# main.net
KiCad netlist of a schematic drawn in EAGLE
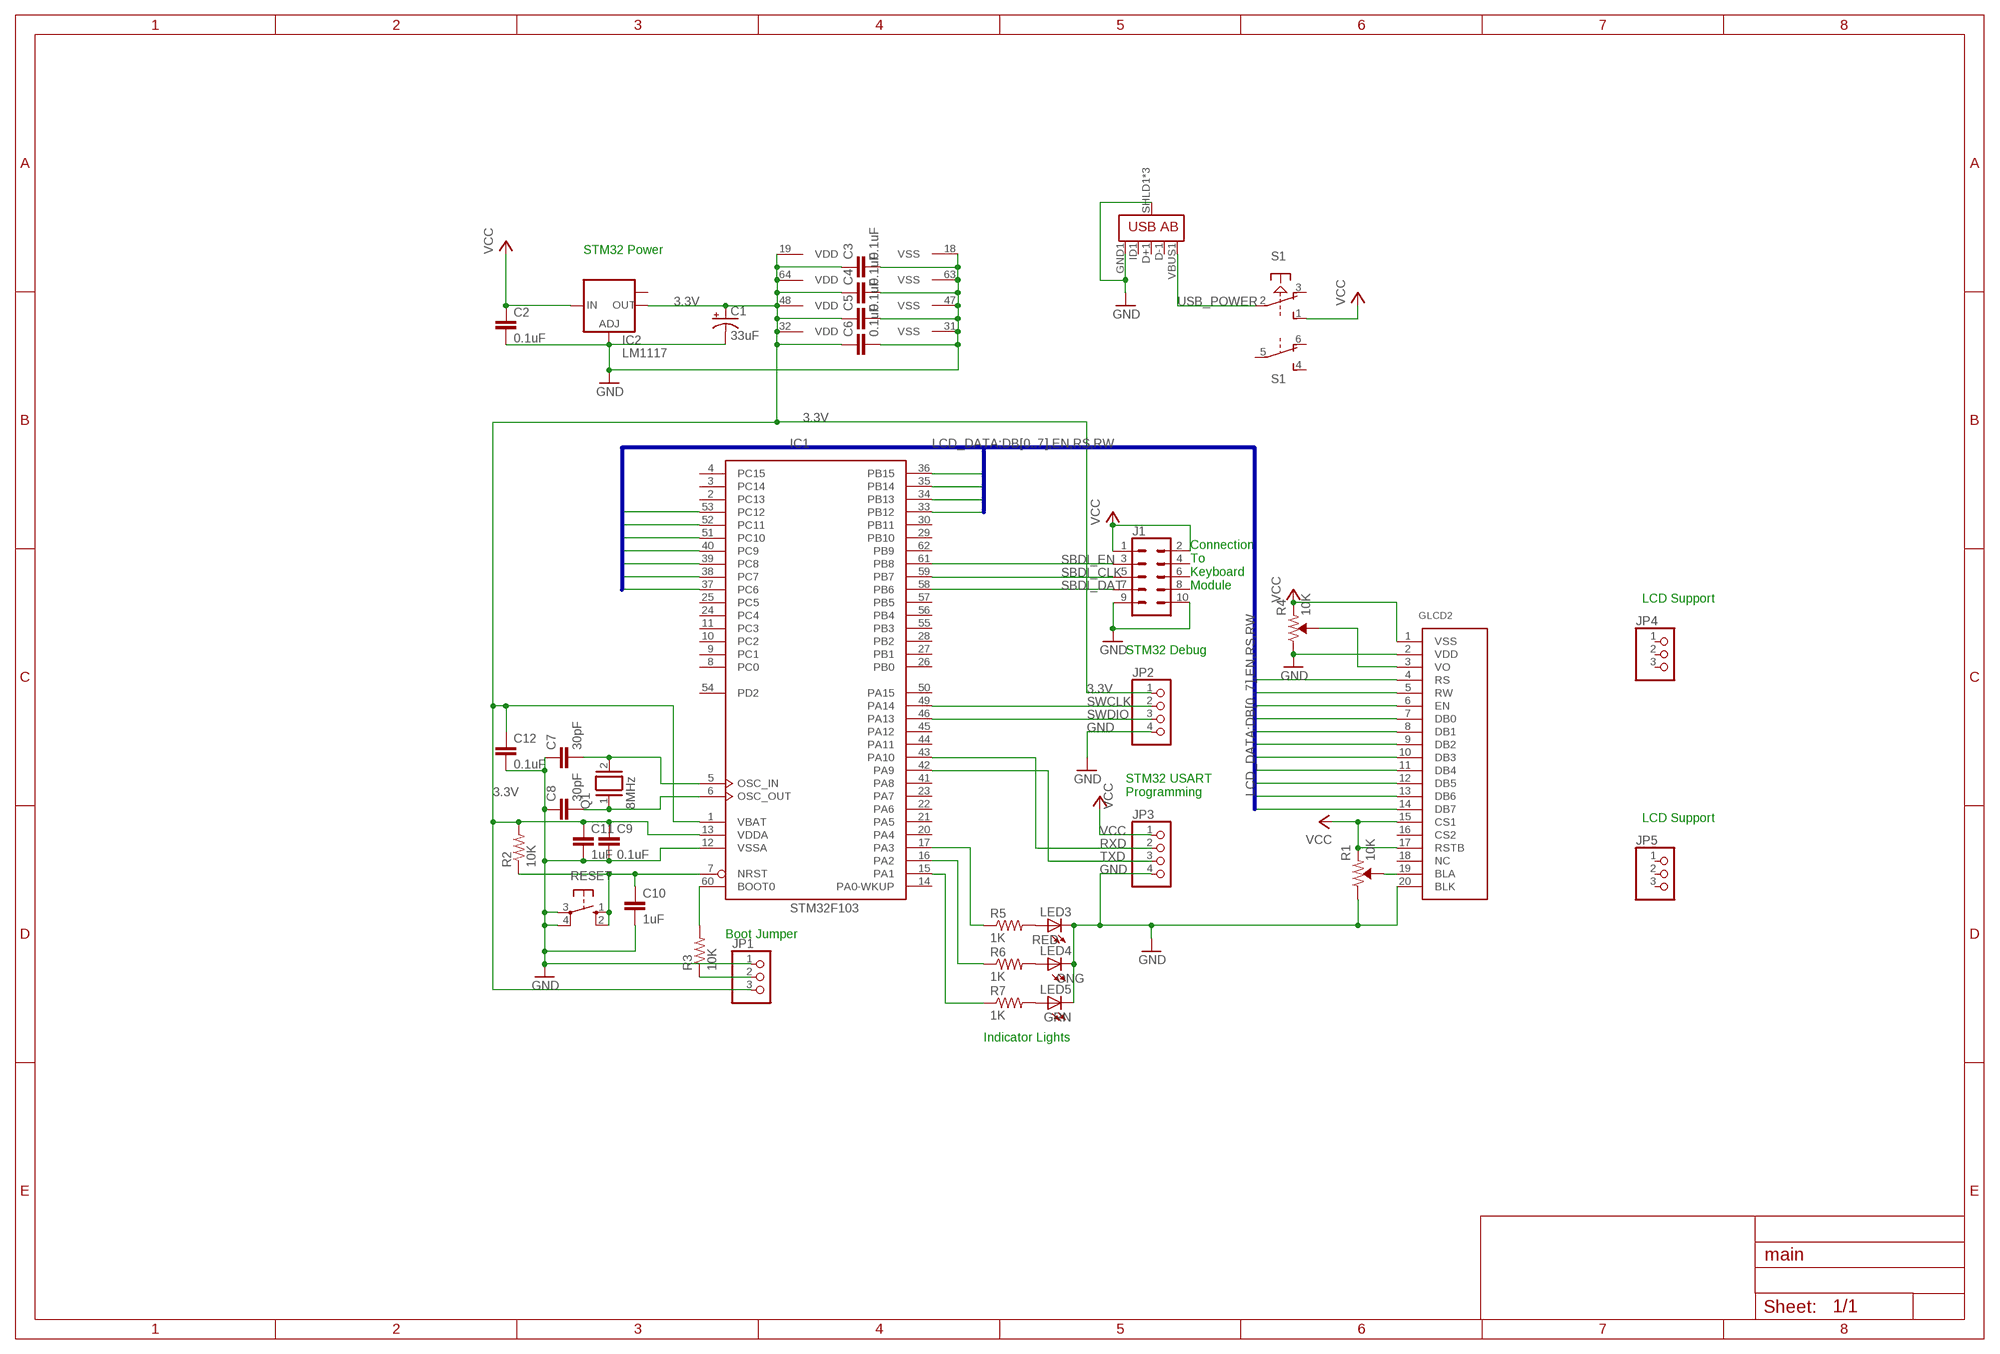
[diagram p0: schematic, sheet 1]

(export (version "E")
  (design (tool "Eeschema 10.0.6"))
  (components
    (comp (ref "C1")
      (value "33uF")
      (footprint "eagle-import:E2-5")
      (libsource (lib "eagle-import") (part "CPOL-USE2-5"))
    )
    (comp (ref "C2")
      (value "0.1uF")
      (footprint "eagle-import:C025-025X050")
      (libsource (lib "eagle-import") (part "C-EU025-025X050"))
    )
    (comp (ref "C3")
      (value "0.1uF")
      (footprint "eagle-import:C025-025X050")
      (libsource (lib "eagle-import") (part "C-EU025-025X050"))
    )
    (comp (ref "C4")
      (value "0.1uF")
      (footprint "eagle-import:C025-025X050")
      (libsource (lib "eagle-import") (part "C-EU025-025X050"))
    )
    (comp (ref "C5")
      (value "0.1uF")
      (footprint "eagle-import:C025-025X050")
      (libsource (lib "eagle-import") (part "C-EU025-025X050"))
    )
    (comp (ref "C6")
      (value "0.1uF")
      (footprint "eagle-import:C025-025X050")
      (libsource (lib "eagle-import") (part "C-EU025-025X050"))
    )
    (comp (ref "C7")
      (value "30pF")
      (footprint "eagle-import:C025-025X050")
      (libsource (lib "eagle-import") (part "C-EU025-025X050"))
    )
    (comp (ref "C8")
      (value "30pF")
      (footprint "eagle-import:C025-025X050")
      (libsource (lib "eagle-import") (part "C-EU025-025X050"))
    )
    (comp (ref "C9")
      (value "0.1uF")
      (footprint "eagle-import:C025-025X050")
      (libsource (lib "eagle-import") (part "C-EU025-025X050"))
    )
    (comp (ref "C10")
      (value "1uF")
      (footprint "eagle-import:C025-025X050")
      (libsource (lib "eagle-import") (part "C-EU025-025X050"))
    )
    (comp (ref "C11")
      (value "1uF")
      (footprint "eagle-import:C025-025X050")
      (libsource (lib "eagle-import") (part "C-EU025-025X050"))
    )
    (comp (ref "C12")
      (value "0.1uF")
      (footprint "eagle-import:C025-025X050")
      (libsource (lib "eagle-import") (part "C-EU025-025X050"))
    )
    (comp (ref "GLCD2")
      (value "LCD128X64")
      (footprint "eagle-import:GLCD_TRULY_128X64_20_PINES")
      (libsource (lib "eagle-import") (part "LCD128X64"))
    )
    (comp (ref "IC1")
      (value "STM32F103")
      (footprint "eagle-import:LQFP64")
      (libsource (lib "eagle-import") (part "STM32F103RTC"))
    )
    (comp (ref "IC2")
      (value "LM1117")
      (footprint "eagle-import:SOT223")
      (libsource (lib "eagle-import") (part "LM1117IMPX-ADJ"))
    )
    (comp (ref "J1")
      (value "CONN_05X2SHD_LOCK")
      (footprint "eagle-import:2X5-SHROUDED_LOCK")
      (libsource (lib "eagle-import") (part "CONN_05X2SHD_LOCK"))
    )
    (comp (ref "JP1")
      (value "PINHD-1X3")
      (footprint "eagle-import:1X03")
      (libsource (lib "eagle-import") (part "PINHD-1X3"))
    )
    (comp (ref "JP2")
      (value "PINHD-1X4")
      (footprint "eagle-import:1X04")
      (libsource (lib "eagle-import") (part "PINHD-1X4"))
    )
    (comp (ref "JP3")
      (value "PINHD-1X4")
      (footprint "eagle-import:1X04")
      (libsource (lib "eagle-import") (part "PINHD-1X4"))
    )
    (comp (ref "JP4")
      (value "PINHD-1X3")
      (footprint "eagle-import:1X03")
      (libsource (lib "eagle-import") (part "PINHD-1X3"))
    )
    (comp (ref "JP5")
      (value "PINHD-1X3")
      (footprint "eagle-import:1X03")
      (libsource (lib "eagle-import") (part "PINHD-1X3"))
    )
    (comp (ref "LED3")
      (value "RED")
      (footprint "eagle-import:LED5MM")
      (libsource (lib "eagle-import") (part "LED5MM"))
    )
    (comp (ref "LED4")
      (value "ONG")
      (footprint "eagle-import:LED5MM")
      (libsource (lib "eagle-import") (part "LED5MM"))
    )
    (comp (ref "LED5")
      (value "GRN")
      (footprint "eagle-import:LED5MM")
      (libsource (lib "eagle-import") (part "LED5MM"))
    )
    (comp (ref "Q1")
      (value "8MHz")
      (footprint "eagle-import:QS")
      (libsource (lib "eagle-import") (part "XTAL/S"))
    )
    (comp (ref "R1")
      (value "10K")
      (footprint "eagle-import:TRIMPOT-PTH-3386U")
      (libsource (lib "eagle-import") (part "TRIMPOT-KNOB"))
    )
    (comp (ref "R2")
      (value "10K")
      (footprint "eagle-import:0204_7")
      (libsource (lib "eagle-import") (part "R-US_0204/7"))
    )
    (comp (ref "R3")
      (value "10K")
      (footprint "eagle-import:0204_7")
      (libsource (lib "eagle-import") (part "R-US_0204/7"))
    )
    (comp (ref "R4")
      (value "10K")
      (footprint "eagle-import:TRIMPOT-PTH-3386U")
      (libsource (lib "eagle-import") (part "TRIMPOT-KNOB"))
    )
    (comp (ref "R5")
      (value "1K")
      (footprint "eagle-import:0204_7")
      (libsource (lib "eagle-import") (part "R-US_0204/7"))
    )
    (comp (ref "R6")
      (value "1K")
      (footprint "eagle-import:0204_7")
      (libsource (lib "eagle-import") (part "R-US_0204/7"))
    )
    (comp (ref "R7")
      (value "1K")
      (footprint "eagle-import:0204_7")
      (libsource (lib "eagle-import") (part "R-US_0204/7"))
    )
    (comp (ref "RESET")
      (value "10-XX")
      (footprint "eagle-import:B3F-10XX")
      (fields (field (name "MPN") "B3F-1000"))
      (libsource (lib "eagle-import") (part "10-XX"))
    )
    (comp (ref "S1")
      (value "PVA2R")
      (footprint "eagle-import:PVA2R")
      (libsource (lib "eagle-import") (part "PVA2R"))
    )
    (comp (ref "U1")
      (value "USB_AB_SMT")
      (footprint "eagle-import:USB-AB-MICRO-SMD")
      (libsource (lib "eagle-import") (part "USB_AB_SMT"))
    )
  )
  (nets
    (net (code "1") (name "/3.3V") (class "Default")
      (node (ref "C1") (pin "+") (pinfunction "+_+") (pintype "passive"))
      (node (ref "C11") (pin "1") (pinfunction "1_1") (pintype "passive"))
      (node (ref "C12") (pin "1") (pinfunction "1_1") (pintype "passive"))
      (node (ref "C3") (pin "1") (pinfunction "1_1") (pintype "passive"))
      (node (ref "C4") (pin "1") (pinfunction "1_1") (pintype "passive"))
      (node (ref "C5") (pin "1") (pinfunction "1_1") (pintype "passive"))
      (node (ref "C6") (pin "1") (pinfunction "1_1") (pintype "passive"))
      (node (ref "C9") (pin "1") (pinfunction "1_1") (pintype "passive"))
      (node (ref "IC1") (pin "1") (pinfunction "VBAT_1") (pintype "power_in"))
      (node (ref "IC1") (pin "13") (pinfunction "VDDA_13") (pintype "power_in"))
      (node (ref "IC1") (pin "19") (pinfunction "VDD_19") (pintype "power_in"))
      (node (ref "IC1") (pin "32") (pinfunction "VDD_32") (pintype "power_in"))
      (node (ref "IC1") (pin "48") (pinfunction "VDD_48") (pintype "power_in"))
      (node (ref "IC1") (pin "64") (pinfunction "VDD_64") (pintype "power_in"))
      (node (ref "IC2") (pin "2") (pinfunction "OUT_2") (pintype "passive"))
      (node (ref "JP1") (pin "3") (pinfunction "3_3") (pintype "passive"))
      (node (ref "JP2") (pin "1") (pinfunction "1_1") (pintype "passive"))
      (node (ref "R2") (pin "2") (pinfunction "2_2") (pintype "passive"))
    )
    (net (code "2") (name "/DB0") (class "Default")
      (node (ref "GLCD2") (pin "7") (pinfunction "DB0_7") (pintype "bidirectional"))
      (node (ref "IC1") (pin "33") (pinfunction "PB12_33") (pintype "bidirectional"))
    )
    (net (code "3") (name "/DB1") (class "Default")
      (node (ref "GLCD2") (pin "8") (pinfunction "DB1_8") (pintype "bidirectional"))
      (node (ref "IC1") (pin "34") (pinfunction "PB13_34") (pintype "bidirectional"))
    )
    (net (code "4") (name "/DB2") (class "Default")
      (node (ref "GLCD2") (pin "9") (pinfunction "DB2_9") (pintype "bidirectional"))
      (node (ref "IC1") (pin "35") (pinfunction "PB14_35") (pintype "bidirectional"))
    )
    (net (code "5") (name "/DB3") (class "Default")
      (node (ref "GLCD2") (pin "10") (pinfunction "DB3_10") (pintype "bidirectional"))
      (node (ref "IC1") (pin "36") (pinfunction "PB15_36") (pintype "bidirectional"))
    )
    (net (code "6") (name "/DB4") (class "Default")
      (node (ref "GLCD2") (pin "11") (pinfunction "DB4_11") (pintype "bidirectional"))
      (node (ref "IC1") (pin "37") (pinfunction "PC6_37") (pintype "bidirectional"))
    )
    (net (code "7") (name "/DB5") (class "Default")
      (node (ref "GLCD2") (pin "12") (pinfunction "DB5_12") (pintype "bidirectional"))
      (node (ref "IC1") (pin "38") (pinfunction "PC7_38") (pintype "bidirectional"))
    )
    (net (code "8") (name "/DB6") (class "Default")
      (node (ref "GLCD2") (pin "13") (pinfunction "DB6_13") (pintype "bidirectional"))
      (node (ref "IC1") (pin "39") (pinfunction "PC8_39") (pintype "bidirectional"))
    )
    (net (code "9") (name "/DB7") (class "Default")
      (node (ref "GLCD2") (pin "14") (pinfunction "DB7_14") (pintype "bidirectional"))
      (node (ref "IC1") (pin "40") (pinfunction "PC9_40") (pintype "bidirectional"))
    )
    (net (code "10") (name "/EN") (class "Default")
      (node (ref "GLCD2") (pin "6") (pinfunction "EN_6") (pintype "bidirectional"))
      (node (ref "IC1") (pin "53") (pinfunction "PC12_53") (pintype "bidirectional"))
    )
    (net (code "11") (name "/RS") (class "Default")
      (node (ref "GLCD2") (pin "4") (pinfunction "RS_4") (pintype "bidirectional"))
      (node (ref "IC1") (pin "51") (pinfunction "PC10_51") (pintype "bidirectional"))
    )
    (net (code "12") (name "/RW") (class "Default")
      (node (ref "GLCD2") (pin "5") (pinfunction "RW_5") (pintype "bidirectional"))
      (node (ref "IC1") (pin "52") (pinfunction "PC11_52") (pintype "bidirectional"))
    )
    (net (code "13") (name "/RXD") (class "Default")
      (node (ref "IC1") (pin "43") (pinfunction "PA10_43") (pintype "bidirectional"))
      (node (ref "JP3") (pin "2") (pinfunction "2_2") (pintype "passive"))
    )
    (net (code "14") (name "/SBDI_CLK") (class "Default")
      (node (ref "IC1") (pin "59") (pinfunction "PB7_59") (pintype "bidirectional"))
      (node (ref "J1") (pin "5") (pinfunction "5_5") (pintype "passive"))
    )
    (net (code "15") (name "/SBDI_DAT") (class "Default")
      (node (ref "IC1") (pin "58") (pinfunction "PB6_58") (pintype "bidirectional"))
      (node (ref "J1") (pin "7") (pinfunction "7_7") (pintype "passive"))
    )
    (net (code "16") (name "/SBDI_EN") (class "Default")
      (node (ref "IC1") (pin "61") (pinfunction "PB8_61") (pintype "bidirectional"))
      (node (ref "J1") (pin "3") (pinfunction "3_3") (pintype "passive"))
    )
    (net (code "17") (name "/SWCLK") (class "Default")
      (node (ref "IC1") (pin "49") (pinfunction "PA14_49") (pintype "bidirectional"))
      (node (ref "JP2") (pin "2") (pinfunction "2_2") (pintype "passive"))
    )
    (net (code "18") (name "/SWDIO") (class "Default")
      (node (ref "IC1") (pin "46") (pinfunction "PA13_46") (pintype "bidirectional"))
      (node (ref "JP2") (pin "3") (pinfunction "3_3") (pintype "passive"))
    )
    (net (code "19") (name "/TXD") (class "Default")
      (node (ref "IC1") (pin "42") (pinfunction "PA9_42") (pintype "bidirectional"))
      (node (ref "JP3") (pin "3") (pinfunction "3_3") (pintype "passive"))
    )
    (net (code "20") (name "/USB_POWER") (class "Default")
      (node (ref "S1") (pin "2") (pinfunction "P_2") (pintype "passive"))
      (node (ref "U1") (pin "VBUS1") (pinfunction "VBUS_VBUS1") (pintype "power_in"))
    )
    (net (code "22") (name "GND") (class "Default")
      (node (ref "C1") (pin "-") (pinfunction "-_-") (pintype "passive"))
      (node (ref "C10") (pin "2") (pinfunction "2_2") (pintype "passive"))
      (node (ref "C11") (pin "2") (pinfunction "2_2") (pintype "passive"))
      (node (ref "C12") (pin "2") (pinfunction "2_2") (pintype "passive"))
      (node (ref "C2") (pin "2") (pinfunction "2_2") (pintype "passive"))
      (node (ref "C3") (pin "2") (pinfunction "2_2") (pintype "passive"))
      (node (ref "C4") (pin "2") (pinfunction "2_2") (pintype "passive"))
      (node (ref "C5") (pin "2") (pinfunction "2_2") (pintype "passive"))
      (node (ref "C6") (pin "2") (pinfunction "2_2") (pintype "passive"))
      (node (ref "C7") (pin "1") (pinfunction "1_1") (pintype "passive"))
      (node (ref "C8") (pin "1") (pinfunction "1_1") (pintype "passive"))
      (node (ref "C9") (pin "2") (pinfunction "2_2") (pintype "passive"))
      (node (ref "GLCD2") (pin "2") (pinfunction "VDD_2") (pintype "power_in"))
      (node (ref "GLCD2") (pin "20") (pinfunction "BLK_20") (pintype "power_in"))
      (node (ref "IC1") (pin "12") (pinfunction "VSSA_12") (pintype "power_in"))
      (node (ref "IC1") (pin "18") (pinfunction "VSS_18") (pintype "power_in"))
      (node (ref "IC1") (pin "31") (pinfunction "VSS_31") (pintype "power_in"))
      (node (ref "IC1") (pin "47") (pinfunction "VSS_47") (pintype "power_in"))
      (node (ref "IC1") (pin "63") (pinfunction "VSS_63") (pintype "power_in"))
      (node (ref "IC2") (pin "1") (pinfunction "ADJ_1") (pintype "input"))
      (node (ref "J1") (pin "10") (pinfunction "10_10") (pintype "passive"))
      (node (ref "J1") (pin "9") (pinfunction "9_9") (pintype "passive"))
      (node (ref "JP1") (pin "1") (pinfunction "1_1") (pintype "passive"))
      (node (ref "JP2") (pin "4") (pinfunction "4_4") (pintype "passive"))
      (node (ref "JP3") (pin "4") (pinfunction "4_4") (pintype "passive"))
      (node (ref "LED3") (pin "K") (pinfunction "C_K") (pintype "passive"))
      (node (ref "LED4") (pin "K") (pinfunction "C_K") (pintype "passive"))
      (node (ref "LED5") (pin "K") (pinfunction "C_K") (pintype "passive"))
      (node (ref "R1") (pin "1") (pinfunction "1_1") (pintype "passive"))
      (node (ref "R4") (pin "1") (pinfunction "1_1") (pintype "passive"))
      (node (ref "RESET") (pin "3") (pinfunction "P_3") (pintype "passive"))
      (node (ref "RESET") (pin "4") (pinfunction "P1_4") (pintype "passive"))
      (node (ref "U1") (pin "GND1") (pinfunction "GND_GND1") (pintype "power_in"))
      (node (ref "U1") (pin "SHLD1") (pinfunction "SHIELD_SHLD1") (pintype "bidirectional"))
      (node (ref "U1") (pin "SHLD2") (pinfunction "SHIELD_SHLD2") (pintype "bidirectional"))
      (node (ref "U1") (pin "SHLD3") (pinfunction "SHIELD_SHLD3") (pintype "bidirectional"))
    )
    (net (code "23") (name "Net-(GLCD2-BLA)") (class "Default")
      (node (ref "GLCD2") (pin "19") (pinfunction "BLA_19") (pintype "power_in"))
      (node (ref "R1") (pin "2") (pinfunction "2_2") (pintype "passive"))
    )
    (net (code "24") (name "Net-(GLCD2-VO)") (class "Default")
      (node (ref "GLCD2") (pin "3") (pinfunction "VO_3") (pintype "bidirectional"))
      (node (ref "R4") (pin "2") (pinfunction "2_2") (pintype "passive"))
    )
    (net (code "25") (name "Net-(IC1A-BOOT0)") (class "Default")
      (node (ref "IC1") (pin "60") (pinfunction "BOOT0_60") (pintype "input"))
      (node (ref "R3") (pin "2") (pinfunction "2_2") (pintype "passive"))
    )
    (net (code "26") (name "Net-(IC1A-NRST)") (class "Default")
      (node (ref "C10") (pin "1") (pinfunction "1_1") (pintype "passive"))
      (node (ref "IC1") (pin "7") (pinfunction "NRST_7") (pintype "bidirectional"))
      (node (ref "R2") (pin "1") (pinfunction "1_1") (pintype "passive"))
      (node (ref "RESET") (pin "1") (pinfunction "S_1") (pintype "passive"))
      (node (ref "RESET") (pin "2") (pinfunction "S1_2") (pintype "passive"))
    )
    (net (code "27") (name "Net-(IC1A-OSC_IN)") (class "Default")
      (node (ref "C7") (pin "2") (pinfunction "2_2") (pintype "passive"))
      (node (ref "IC1") (pin "5") (pinfunction "OSC_IN_5") (pintype "bidirectional"))
      (node (ref "Q1") (pin "2") (pinfunction "2_2") (pintype "passive"))
    )
    (net (code "28") (name "Net-(IC1A-OSC_OUT)") (class "Default")
      (node (ref "C8") (pin "2") (pinfunction "2_2") (pintype "passive"))
      (node (ref "IC1") (pin "6") (pinfunction "OSC_OUT_6") (pintype "bidirectional"))
      (node (ref "Q1") (pin "1") (pinfunction "1_1") (pintype "passive"))
    )
    (net (code "29") (name "Net-(IC1A-PA1)") (class "Default")
      (node (ref "IC1") (pin "15") (pinfunction "PA1_15") (pintype "bidirectional"))
      (node (ref "R7") (pin "1") (pinfunction "1_1") (pintype "passive"))
    )
    (net (code "30") (name "Net-(IC1A-PA2)") (class "Default")
      (node (ref "IC1") (pin "16") (pinfunction "PA2_16") (pintype "bidirectional"))
      (node (ref "R6") (pin "1") (pinfunction "1_1") (pintype "passive"))
    )
    (net (code "31") (name "Net-(IC1A-PA3)") (class "Default")
      (node (ref "IC1") (pin "17") (pinfunction "PA3_17") (pintype "bidirectional"))
      (node (ref "R5") (pin "1") (pinfunction "1_1") (pintype "passive"))
    )
    (net (code "32") (name "Net-(JP1-Pad2)") (class "Default")
      (node (ref "JP1") (pin "2") (pinfunction "2_2") (pintype "passive"))
      (node (ref "R3") (pin "1") (pinfunction "1_1") (pintype "passive"))
    )
    (net (code "33") (name "Net-(LED3-PadA)") (class "Default")
      (node (ref "LED3") (pin "A") (pinfunction "A_A") (pintype "passive"))
      (node (ref "R5") (pin "2") (pinfunction "2_2") (pintype "passive"))
    )
    (net (code "34") (name "Net-(LED4-PadA)") (class "Default")
      (node (ref "LED4") (pin "A") (pinfunction "A_A") (pintype "passive"))
      (node (ref "R6") (pin "2") (pinfunction "2_2") (pintype "passive"))
    )
    (net (code "35") (name "Net-(LED5-PadA)") (class "Default")
      (node (ref "LED5") (pin "A") (pinfunction "A_A") (pintype "passive"))
      (node (ref "R7") (pin "2") (pinfunction "2_2") (pintype "passive"))
    )
    (net (code "36") (name "VCC") (class "Default")
      (node (ref "C2") (pin "1") (pinfunction "1_1") (pintype "passive"))
      (node (ref "GLCD2") (pin "1") (pinfunction "VSS_1") (pintype "power_in"))
      (node (ref "GLCD2") (pin "15") (pinfunction "CS1_15") (pintype "bidirectional"))
      (node (ref "GLCD2") (pin "17") (pinfunction "RSTB_17") (pintype "bidirectional"))
      (node (ref "IC2") (pin "3") (pinfunction "IN_3") (pintype "input"))
      (node (ref "J1") (pin "1") (pinfunction "1_1") (pintype "passive"))
      (node (ref "J1") (pin "2") (pinfunction "2_2") (pintype "passive"))
      (node (ref "JP3") (pin "1") (pinfunction "1_1") (pintype "passive"))
      (node (ref "R1") (pin "3") (pinfunction "3_3") (pintype "passive"))
      (node (ref "R4") (pin "3") (pinfunction "3_3") (pintype "passive"))
      (node (ref "S1") (pin "1") (pinfunction "S_1") (pintype "passive"))
    )
    (net (code "37") (name "unconnected-(GLCD2-CS2-Pad16)") (class "Default")
      (node (ref "GLCD2") (pin "16") (pinfunction "CS2_16") (pintype "bidirectional"))
    )
    (net (code "38") (name "unconnected-(GLCD2-NC-Pad18)") (class "Default")
      (node (ref "GLCD2") (pin "18") (pinfunction "NC_18") (pintype "bidirectional"))
    )
    (net (code "39") (name "unconnected-(IC1A-PA0-WKUP-Pad14)") (class "Default")
      (node (ref "IC1") (pin "14") (pinfunction "PA0-WKUP_14") (pintype "bidirectional"))
    )
    (net (code "40") (name "unconnected-(IC1A-PA4-Pad20)") (class "Default")
      (node (ref "IC1") (pin "20") (pinfunction "PA4_20") (pintype "bidirectional"))
    )
    (net (code "41") (name "unconnected-(IC1A-PA5-Pad21)") (class "Default")
      (node (ref "IC1") (pin "21") (pinfunction "PA5_21") (pintype "bidirectional"))
    )
    (net (code "42") (name "unconnected-(IC1A-PA6-Pad22)") (class "Default")
      (node (ref "IC1") (pin "22") (pinfunction "PA6_22") (pintype "bidirectional"))
    )
    (net (code "43") (name "unconnected-(IC1A-PA7-Pad23)") (class "Default")
      (node (ref "IC1") (pin "23") (pinfunction "PA7_23") (pintype "bidirectional"))
    )
    (net (code "44") (name "unconnected-(IC1A-PA8-Pad41)") (class "Default")
      (node (ref "IC1") (pin "41") (pinfunction "PA8_41") (pintype "bidirectional"))
    )
    (net (code "45") (name "unconnected-(IC1A-PA11-Pad44)") (class "Default")
      (node (ref "IC1") (pin "44") (pinfunction "PA11_44") (pintype "bidirectional"))
    )
    (net (code "46") (name "unconnected-(IC1A-PA12-Pad45)") (class "Default")
      (node (ref "IC1") (pin "45") (pinfunction "PA12_45") (pintype "bidirectional"))
    )
    (net (code "47") (name "unconnected-(IC1A-PA15-Pad50)") (class "Default")
      (node (ref "IC1") (pin "50") (pinfunction "PA15_50") (pintype "bidirectional"))
    )
    (net (code "48") (name "unconnected-(IC1A-PB0-Pad26)") (class "Default")
      (node (ref "IC1") (pin "26") (pinfunction "PB0_26") (pintype "bidirectional"))
    )
    (net (code "49") (name "unconnected-(IC1A-PB1-Pad27)") (class "Default")
      (node (ref "IC1") (pin "27") (pinfunction "PB1_27") (pintype "bidirectional"))
    )
    (net (code "50") (name "unconnected-(IC1A-PB2-Pad28)") (class "Default")
      (node (ref "IC1") (pin "28") (pinfunction "PB2_28") (pintype "bidirectional"))
    )
    (net (code "51") (name "unconnected-(IC1A-PB3-Pad55)") (class "Default")
      (node (ref "IC1") (pin "55") (pinfunction "PB3_55") (pintype "bidirectional"))
    )
    (net (code "52") (name "unconnected-(IC1A-PB4-Pad56)") (class "Default")
      (node (ref "IC1") (pin "56") (pinfunction "PB4_56") (pintype "bidirectional"))
    )
    (net (code "53") (name "unconnected-(IC1A-PB5-Pad57)") (class "Default")
      (node (ref "IC1") (pin "57") (pinfunction "PB5_57") (pintype "bidirectional"))
    )
    (net (code "54") (name "unconnected-(IC1A-PB9-Pad62)") (class "Default")
      (node (ref "IC1") (pin "62") (pinfunction "PB9_62") (pintype "bidirectional"))
    )
    (net (code "55") (name "unconnected-(IC1A-PB10-Pad29)") (class "Default")
      (node (ref "IC1") (pin "29") (pinfunction "PB10_29") (pintype "bidirectional"))
    )
    (net (code "56") (name "unconnected-(IC1A-PB11-Pad30)") (class "Default")
      (node (ref "IC1") (pin "30") (pinfunction "PB11_30") (pintype "bidirectional"))
    )
    (net (code "57") (name "unconnected-(IC1A-PC0-Pad8)") (class "Default")
      (node (ref "IC1") (pin "8") (pinfunction "PC0_8") (pintype "bidirectional"))
    )
    (net (code "58") (name "unconnected-(IC1A-PC1-Pad9)") (class "Default")
      (node (ref "IC1") (pin "9") (pinfunction "PC1_9") (pintype "bidirectional"))
    )
    (net (code "59") (name "unconnected-(IC1A-PC2-Pad10)") (class "Default")
      (node (ref "IC1") (pin "10") (pinfunction "PC2_10") (pintype "bidirectional"))
    )
    (net (code "60") (name "unconnected-(IC1A-PC3-Pad11)") (class "Default")
      (node (ref "IC1") (pin "11") (pinfunction "PC3_11") (pintype "bidirectional"))
    )
    (net (code "61") (name "unconnected-(IC1A-PC4-Pad24)") (class "Default")
      (node (ref "IC1") (pin "24") (pinfunction "PC4_24") (pintype "bidirectional"))
    )
    (net (code "62") (name "unconnected-(IC1A-PC5-Pad25)") (class "Default")
      (node (ref "IC1") (pin "25") (pinfunction "PC5_25") (pintype "bidirectional"))
    )
    (net (code "63") (name "unconnected-(IC1A-PC13-Pad2)") (class "Default")
      (node (ref "IC1") (pin "2") (pinfunction "PC13_2") (pintype "bidirectional"))
    )
    (net (code "64") (name "unconnected-(IC1A-PC14-Pad3)") (class "Default")
      (node (ref "IC1") (pin "3") (pinfunction "PC14_3") (pintype "bidirectional"))
    )
    (net (code "65") (name "unconnected-(IC1A-PC15-Pad4)") (class "Default")
      (node (ref "IC1") (pin "4") (pinfunction "PC15_4") (pintype "bidirectional"))
    )
    (net (code "66") (name "unconnected-(IC1A-PD2-Pad54)") (class "Default")
      (node (ref "IC1") (pin "54") (pinfunction "PD2_54") (pintype "bidirectional"))
    )
    (net (code "67") (name "unconnected-(IC2-OUT1-PadTAB)") (class "Default")
      (node (ref "IC2") (pin "TAB") (pinfunction "OUT1_TAB") (pintype "passive"))
    )
    (net (code "68") (name "unconnected-(J1-Pad4)") (class "Default")
      (node (ref "J1") (pin "4") (pinfunction "4_4") (pintype "passive"))
    )
    (net (code "69") (name "unconnected-(J1-Pad6)") (class "Default")
      (node (ref "J1") (pin "6") (pinfunction "6_6") (pintype "passive"))
    )
    (net (code "70") (name "unconnected-(J1-Pad8)") (class "Default")
      (node (ref "J1") (pin "8") (pinfunction "8_8") (pintype "passive"))
    )
    (net (code "71") (name "unconnected-(JP4-Pad1)") (class "Default")
      (node (ref "JP4") (pin "1") (pinfunction "1_1") (pintype "passive"))
    )
    (net (code "72") (name "unconnected-(JP4-Pad2)") (class "Default")
      (node (ref "JP4") (pin "2") (pinfunction "2_2") (pintype "passive"))
    )
    (net (code "73") (name "unconnected-(JP4-Pad3)") (class "Default")
      (node (ref "JP4") (pin "3") (pinfunction "3_3") (pintype "passive"))
    )
    (net (code "74") (name "unconnected-(JP5-Pad1)") (class "Default")
      (node (ref "JP5") (pin "1") (pinfunction "1_1") (pintype "passive"))
    )
    (net (code "75") (name "unconnected-(JP5-Pad2)") (class "Default")
      (node (ref "JP5") (pin "2") (pinfunction "2_2") (pintype "passive"))
    )
    (net (code "76") (name "unconnected-(JP5-Pad3)") (class "Default")
      (node (ref "JP5") (pin "3") (pinfunction "3_3") (pintype "passive"))
    )
    (net (code "77") (name "unconnected-(S1A-O-Pad3)") (class "Default")
      (node (ref "S1") (pin "3") (pinfunction "O_3") (pintype "passive"))
    )
    (net (code "78") (name "unconnected-(S1B-O-Pad6)") (class "Default")
      (node (ref "S1") (pin "6") (pinfunction "O_6") (pintype "passive"))
    )
    (net (code "79") (name "unconnected-(S1B-P-Pad5)") (class "Default")
      (node (ref "S1") (pin "5") (pinfunction "P_5") (pintype "passive"))
    )
    (net (code "80") (name "unconnected-(S1B-S-Pad4)") (class "Default")
      (node (ref "S1") (pin "4") (pinfunction "S_4") (pintype "passive"))
    )
    (net (code "81") (name "unconnected-(U1-D+-PadD+1)") (class "Default")
      (node (ref "U1") (pin "D+1") (pinfunction "D+_D+1") (pintype "bidirectional"))
    )
    (net (code "82") (name "unconnected-(U1-D--PadD-1)") (class "Default")
      (node (ref "U1") (pin "D-1") (pinfunction "D-_D-1") (pintype "bidirectional"))
    )
    (net (code "83") (name "unconnected-(U1-USBID-PadID1)") (class "Default")
      (node (ref "U1") (pin "ID1") (pinfunction "USBID_ID1") (pintype "bidirectional"))
    )
  )
)
